# MB1219.net
KiCad netlist of a schematic drawn in Altium Designer
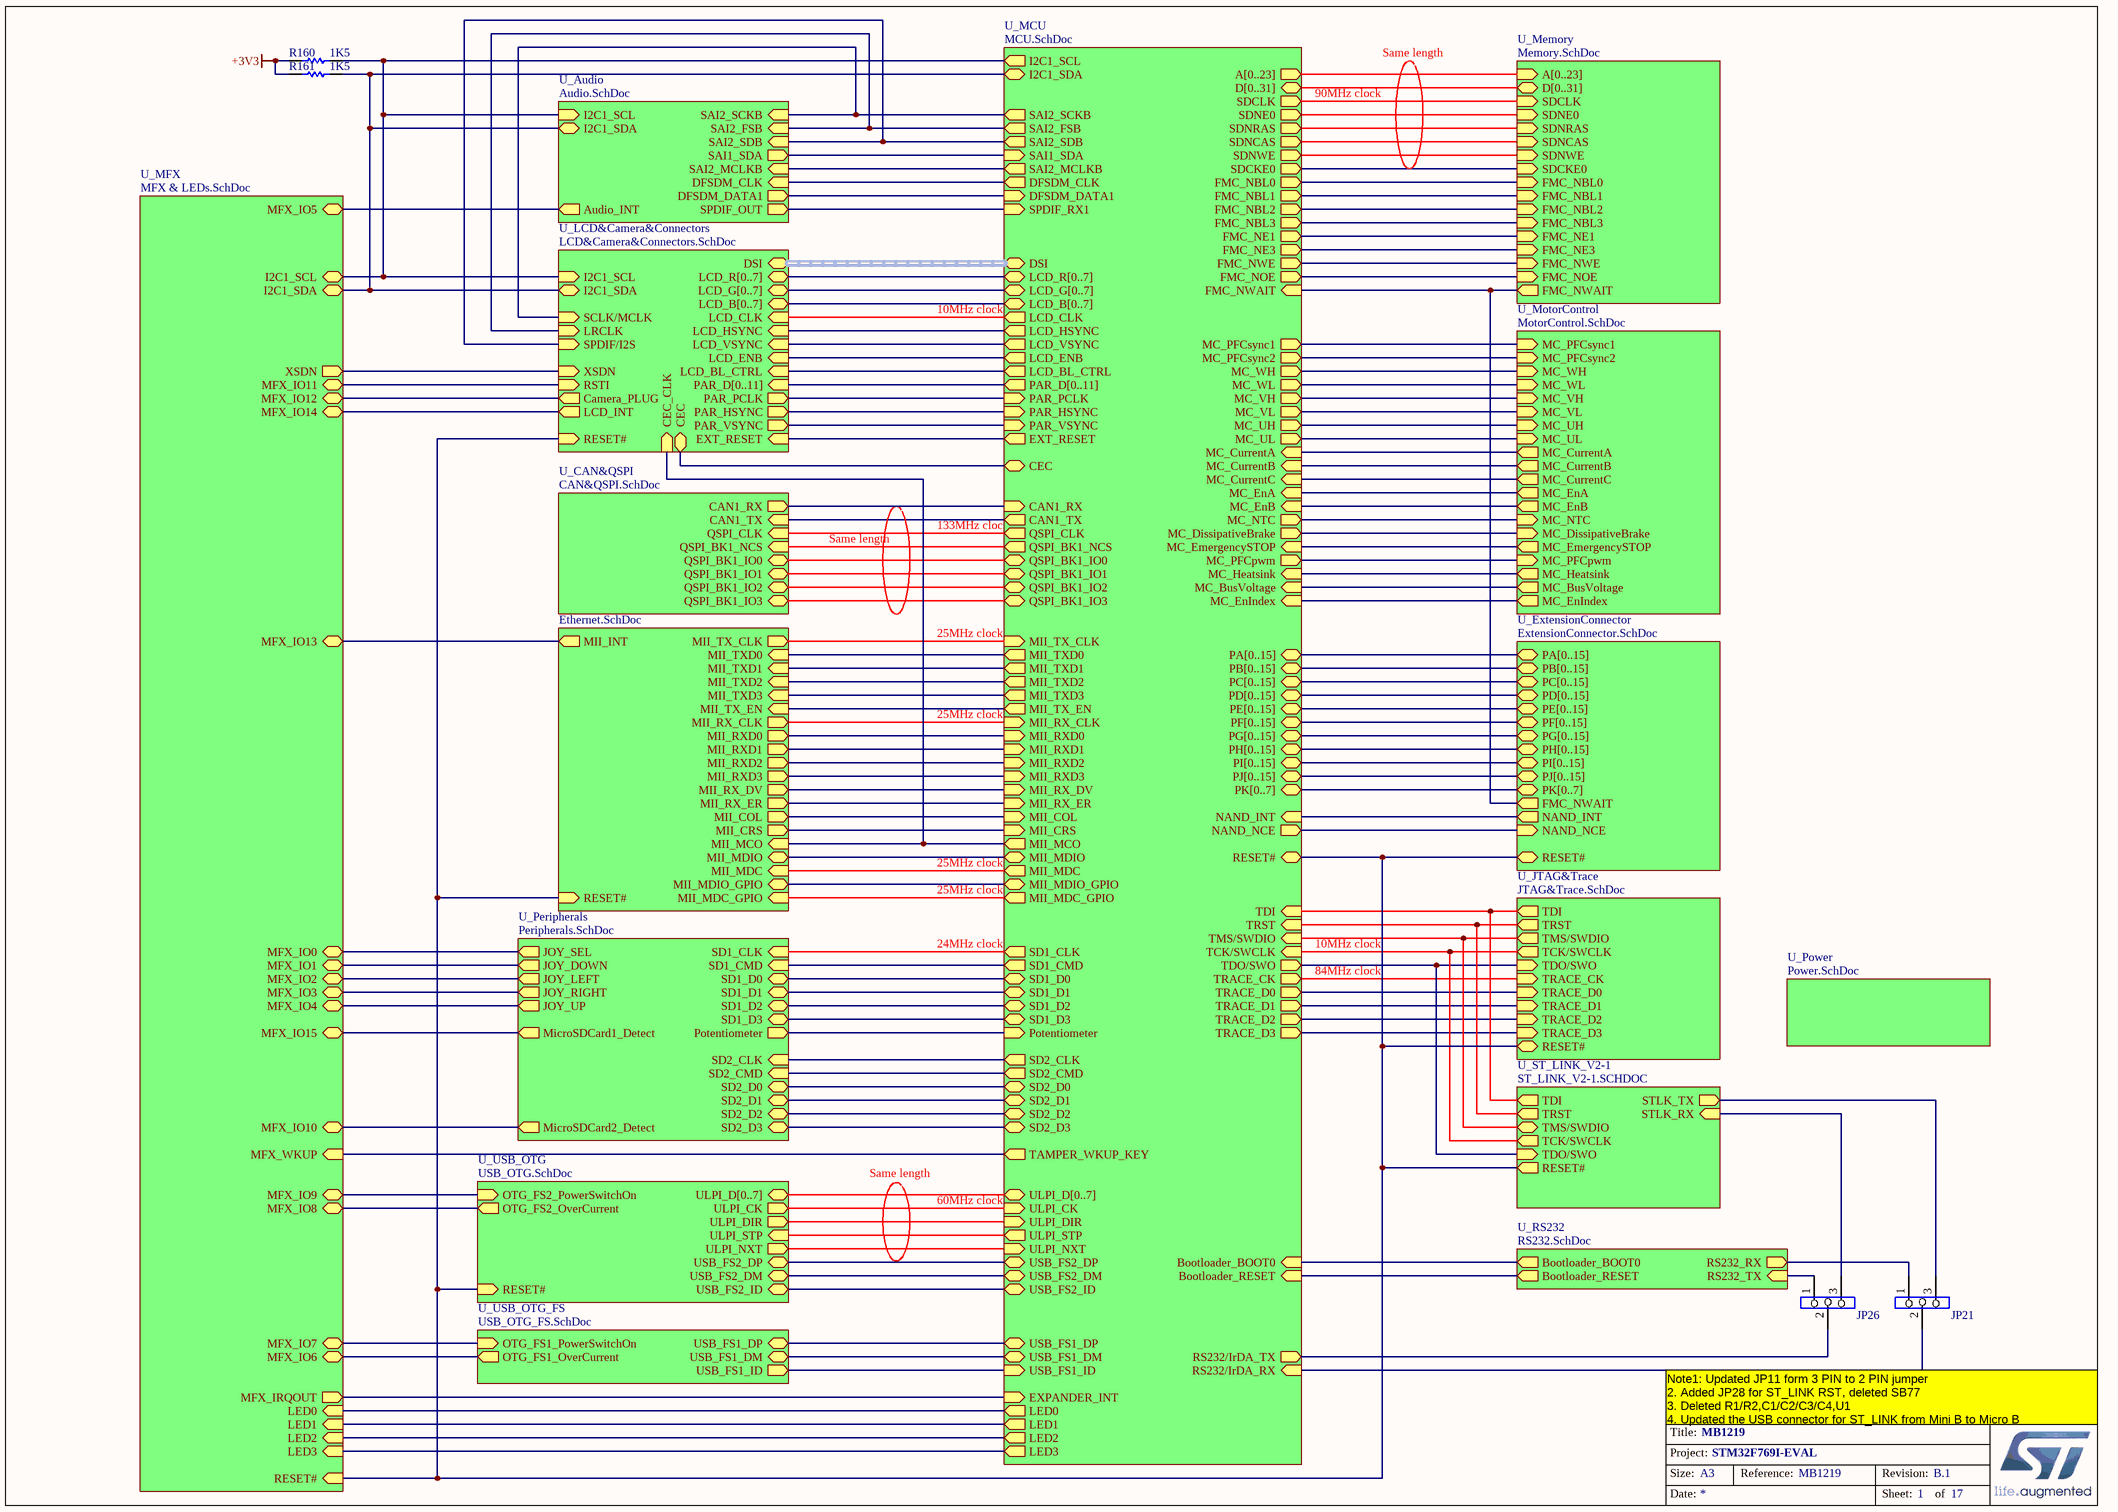
[diagram p0: MB1219.SchDoc]

(export (version "E")
  (design (tool "Eeschema 10.0.6"))
  (components
    (comp (ref "JP21") (value "~") (footprint "SIP3") (libsource (lib "STR910_SCHLIB") (part "Jumper3")))
    (comp (ref "JP26") (value "~") (footprint "SIP3") (libsource (lib "STR910_SCHLIB") (part "Jumper3")))
    (comp (ref "R160")
      (value "1K5")
      (footprint "0603R")
      (description "Resistor")
      (fields (field (name "PUBLISHER") "Altium Limited"))
      (libsource (lib "Miscellaneous Devices") (part "Res1"))
    )
    (comp (ref "R161")
      (value "1K5")
      (footprint "0603R")
      (description "Resistor")
      (fields (field (name "PUBLISHER") "Altium Limited"))
      (libsource (lib "Miscellaneous Devices") (part "Res1"))
    )
  )
  (nets
    (net (code "1") (name "+3V3") (class "Default")
      (node (ref "R160") (pin "1") (pinfunction "1_1") (pintype "passive"))
      (node (ref "R161") (pin "1") (pinfunction "1_1") (pintype "passive"))
    )
    (net (code "24") (name "/I2C1_SCL") (class "Default")
      (node (ref "R160") (pin "2") (pinfunction "2_2") (pintype "passive"))
    )
    (net (code "25") (name "/I2C1_SDA") (class "Default")
      (node (ref "R161") (pin "2") (pinfunction "2_2") (pintype "passive"))
    )
    (net (code "118") (name "/RS232_RX") (class "Default") (node (ref "JP21") (pin "1") (pintype "passive")))
    (net (code "119") (name "/RS232_TX") (class "Default") (node (ref "JP26") (pin "1") (pintype "passive")))
    (net (code "120") (name "/RS232{slash}IrDA_RX") (class "Default")
      (node (ref "JP21") (pin "2") (pintype "passive"))
    )
    (net (code "121") (name "/RS232{slash}IrDA_TX") (class "Default")
      (node (ref "JP26") (pin "2") (pintype "passive"))
    )
    (net (code "146") (name "/STLK_RX") (class "Default") (node (ref "JP26") (pin "3") (pintype "passive")))
    (net (code "147") (name "/STLK_TX") (class "Default") (node (ref "JP21") (pin "3") (pintype "passive")))
  )
)
